# Switch1_copy.net
KiCad netlist of a schematic drawn in Altium Designer
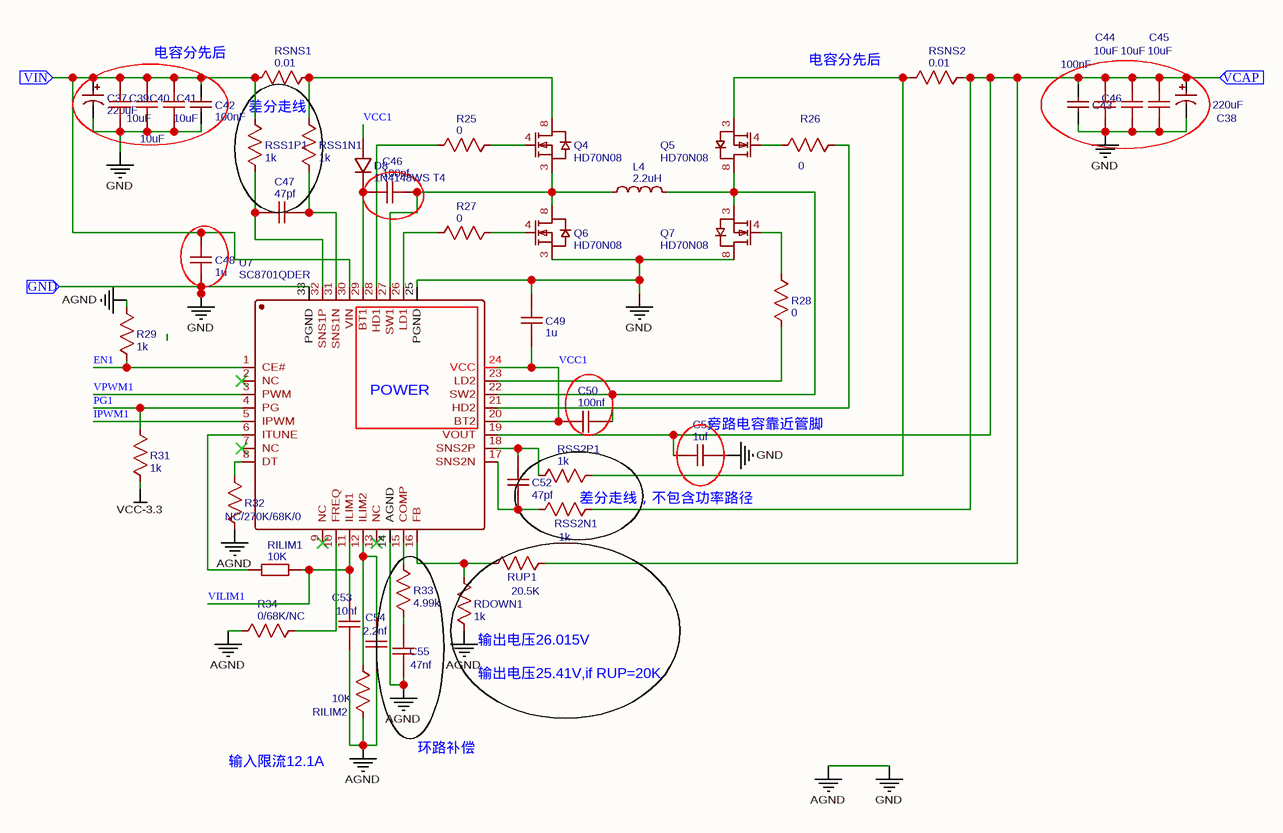
[diagram p0: Switch1 copy.SchDoc]

(export (version "E")
  (design (tool "Eeschema 10.0.6"))
  (components
    (comp (ref "C37")
      (value "220uF")
      (fields
        (field (name "BOM_MANUFACTURER PART") "DV221M050G105A")
        (field (name "BOM_SUPPLIER PART") "C65217")
      )
      (libsource (lib "") (part "root_3_220uF__1"))
    )
    (comp (ref "C38")
      (value "220uF")
      (fields
        (field (name "BOM_MANUFACTURER PART") "DV221M050G105A")
        (field (name "BOM_SUPPLIER PART") "C65217")
      )
      (libsource (lib "altium-import") (part "root_3_220uF_"))
    )
    (comp (ref "C39")
      (value "10uF")
      (fields
        (field (name "BOM_MANUFACTURER PART") "GRM31CR61H106KA12L")
        (field (name "BOM_SUPPLIER PART") "C77092")
      )
      (libsource (lib "altium-import") (part "root_1_10uF_"))
    )
    (comp (ref "C40")
      (value "10uF")
      (fields
        (field (name "BOM_MANUFACTURER PART") "GRM31CR61H106KA12L")
        (field (name "BOM_SUPPLIER PART") "C77092")
      )
      (libsource (lib "altium-import") (part "root_1_10uF_"))
    )
    (comp (ref "C41")
      (value "10uF")
      (fields
        (field (name "BOM_MANUFACTURER PART") "GRM31CR61H106KA12L")
        (field (name "BOM_SUPPLIER PART") "C77092")
      )
      (libsource (lib "altium-import") (part "root_1_10uF_"))
    )
    (comp (ref "C42")
      (value "100nF")
      (fields
        (field (name "BOM_MANUFACTURER PART") "CL10B104JB8NNNC")
        (field (name "BOM_SUPPLIER PART") "C1525")
      )
      (libsource (lib "altium-import") (part "root_1_100nF_"))
    )
    (comp (ref "C43")
      (value "100nF")
      (fields
        (field (name "BOM_MANUFACTURER PART") "CL10B104JB8NNNC")
        (field (name "BOM_SUPPLIER PART") "C1525")
      )
      (libsource (lib "altium-import") (part "root_1_100nF_"))
    )
    (comp (ref "C44")
      (value "10uF")
      (fields
        (field (name "BOM_MANUFACTURER PART") "GRM31CR61H106KA12L")
        (field (name "BOM_SUPPLIER PART") "C77092")
      )
      (libsource (lib "") (part "root_1_10uF__1"))
    )
    (comp (ref "C45")
      (value "10uF")
      (fields
        (field (name "BOM_MANUFACTURER PART") "GRM31CR61H106KA12L")
        (field (name "BOM_SUPPLIER PART") "C77092")
      )
      (libsource (lib "") (part "root_1_10uF__1"))
    )
    (comp (ref "C46") (value "100nf") (libsource (lib "altium-import") (part "root_3_100nf_")))
    (comp (ref "C47")
      (value "47pf")
      (fields (field (name "BOM_SUPPLIER PART") "C1567"))
      (libsource (lib "altium-import") (part "root_1_47pf_"))
    )
    (comp (ref "C48") (value "1u") (libsource (lib "altium-import") (part "root_0_1u_")))
    (comp (ref "C49") (value "1u") (libsource (lib "altium-import") (part "root_0_1u_")))
    (comp (ref "C50") (value "100nf") (libsource (lib "altium-import") (part "root_1_100nf_")))
    (comp (ref "C51") (value "1uf") (libsource (lib "altium-import") (part "root_1_1uf_")))
    (comp (ref "C52")
      (value "47pf")
      (fields (field (name "BOM_SUPPLIER PART") "C1567"))
      (libsource (lib "altium-import") (part "root_2_47pf_"))
    )
    (comp (ref "C53") (value "10nf") (libsource (lib "altium-import") (part "root_0_10nf_")))
    (comp (ref "C54") (value "2.2nf") (libsource (lib "altium-import") (part "root_0_2.2nf_")))
    (comp (ref "C55") (value "47nf") (libsource (lib "altium-import") (part "root_0_47nf_")))
    (comp (ref "D8")
      (value "1N4148WS T4")
      (fields (field (name "BOM_SUPPLIER PART") "C2128"))
      (libsource (lib "altium-import") (part "root_3_1N4148WS T4_"))
    )
    (comp (ref "L4")
      (value "2.2uH")
      (fields
        (field (name "BOM_SUPPLIER PART") "C241452")
        (field (name "BOM_MANUFACTURER PART") "YXMAC1770-2R2M-IGP")
        (field (name "CONTRIBUTOR") "LCSC")
      )
      (libsource (lib "altium-import") (part "root_0_2.2uH_"))
    )
    (comp (ref "NO1")
      (value "10uF")
      (fields
        (field (name "BOM_MANUFACTURER PART") "GRM31CR61H106KA12L")
        (field (name "BOM_SUPPLIER PART") "C77092")
      )
      (libsource (lib "") (part "root_1_10uF__1"))
    )
    (comp (ref "Q4")
      (value "HD70N08")
      (fields (field (name "BOM_SUPPLIER PART") "C190849") (field (name "CONTRIBUTOR") "LCSC"))
      (libsource (lib "altium-import") (part "root_0_HD70N08_"))
    )
    (comp (ref "Q5")
      (value "HD70N08")
      (fields (field (name "BOM_SUPPLIER PART") "C216254") (field (name "CONTRIBUTOR") "LCSC"))
      (libsource (lib "altium-import") (part "root_2_HD70N08_"))
    )
    (comp (ref "Q6")
      (value "HD70N08")
      (fields (field (name "BOM_SUPPLIER PART") "C216254") (field (name "CONTRIBUTOR") "LCSC"))
      (libsource (lib "altium-import") (part "root_0_HD70N08_"))
    )
    (comp (ref "Q7")
      (value "HD70N08")
      (fields (field (name "BOM_SUPPLIER PART") "C216254") (field (name "CONTRIBUTOR") "LCSC"))
      (libsource (lib "altium-import") (part "root_2_HD70N08_"))
    )
    (comp (ref "R25") (value "0") (libsource (lib "altium-import") (part "root_0_0_")))
    (comp (ref "R26") (value "0") (libsource (lib "altium-import") (part "root_0_0_")))
    (comp (ref "R27") (value "0") (libsource (lib "altium-import") (part "root_0_0_")))
    (comp (ref "R28") (value "0") (libsource (lib "altium-import") (part "root_1_0_")))
    (comp (ref "R29") (value "1k") (libsource (lib "altium-import") (part "root_1_1k_")))
    (comp (ref "R31") (value "1k") (libsource (lib "altium-import") (part "root_1_1k_")))
    (comp (ref "R32")
      (value "NC/270K/68K/0")
      (libsource (lib "altium-import") (part "root_1_NC/270K/68K/0_"))
    )
    (comp (ref "R33") (value "4.99k") (libsource (lib "altium-import") (part "root_1_4.99k_")))
    (comp (ref "R34") (value "0/68K/NC") (libsource (lib "altium-import") (part "root_0_0/68K/NC_")))
    (comp (ref "RDOWN1") (value "1k") (libsource (lib "altium-import") (part "root_1_1k_")))
    (comp (ref "RILIM1")
      (value "10K")
      (fields (field (name "BOM_SUPPLIER PART") "C25744") (field (name "CONTRIBUTOR") "LCSC"))
      (libsource (lib "altium-import") (part "root_0_10K_"))
    )
    (comp (ref "RILIM2") (value "10K") (libsource (lib "altium-import") (part "root_1_10K_")))
    (comp (ref "RSNS1")
      (value "0.01")
      (fields (field (name "BOM_SUPPLIER PART") "C236284"))
      (libsource (lib "altium-import") (part "root_0_0.01_"))
    )
    (comp (ref "RSNS2")
      (value "0.01")
      (fields (field (name "BOM_SUPPLIER PART") "C236284"))
      (libsource (lib "altium-import") (part "root_0_0.01_"))
    )
    (comp (ref "RSS1N1")
      (value "1k")
      (fields (field (name "BOM_SUPPLIER PART") "C319809"))
      (libsource (lib "altium-import") (part "root_1_1k_"))
    )
    (comp (ref "RSS1P1")
      (value "1k")
      (fields (field (name "BOM_SUPPLIER PART") "C319809"))
      (libsource (lib "altium-import") (part "root_1_1k_"))
    )
    (comp (ref "RSS2N1")
      (value "1k")
      (fields (field (name "BOM_SUPPLIER PART") "C319809"))
      (libsource (lib "altium-import") (part "root_0_1k_"))
    )
    (comp (ref "RSS2P1")
      (value "1k")
      (fields (field (name "BOM_SUPPLIER PART") "C319809"))
      (libsource (lib "altium-import") (part "root_0_1k_"))
    )
    (comp (ref "RUP1") (value "20.5K") (libsource (lib "altium-import") (part "root_0_20.5K_")))
    (comp (ref "U7")
      (value "SC8701QDER")
      (fields (field (name "BOM_SUPPLIER PART") "C252410") (field (name "CONTRIBUTOR") "LCSC"))
      (libsource (lib "altium-import") (part "root_0_SC8701QDER_"))
    )
  )
  (nets
    (net (code "1") (name "/EN1") (class "Default")
      (node (ref "R29") (pin "1") (pinfunction "1_1") (pintype "passive"))
      (node (ref "U7") (pin "1") (pinfunction "CE#_1") (pintype "passive"))
    )
    (net (code "2") (name "/IPWM1") (class "Default")
      (node (ref "U7") (pin "5") (pinfunction "IPWM_5") (pintype "passive"))
    )
    (net (code "3") (name "/PG1") (class "Default")
      (node (ref "R31") (pin "2") (pinfunction "2_2") (pintype "passive"))
      (node (ref "U7") (pin "4") (pinfunction "PG_4") (pintype "passive"))
    )
    (net (code "4") (name "/VCAP") (class "Default")
      (node (ref "C38") (pin "1") (pinfunction "1_1") (pintype "passive"))
      (node (ref "C43") (pin "2") (pinfunction "2_2") (pintype "passive"))
      (node (ref "C44") (pin "2") (pinfunction "2_2") (pintype "passive"))
      (node (ref "C45") (pin "2") (pinfunction "2_2") (pintype "passive"))
      (node (ref "C51") (pin "2") (pinfunction "2_2") (pintype "passive"))
      (node (ref "NO1") (pin "2") (pinfunction "2_2") (pintype "passive"))
      (node (ref "RSNS2") (pin "2") (pinfunction "2_2") (pintype "passive"))
      (node (ref "RSS2N1") (pin "2") (pinfunction "2_2") (pintype "passive"))
      (node (ref "RUP1") (pin "2") (pinfunction "2_2") (pintype "passive"))
      (node (ref "U7") (pin "19") (pinfunction "VOUT_19") (pintype "passive"))
    )
    (net (code "5") (name "/VCC1") (class "Default")
      (node (ref "C49") (pin "1") (pinfunction "1_1") (pintype "passive"))
      (node (ref "C50") (pin "2") (pinfunction "2_2") (pintype "passive"))
      (node (ref "D8") (pin "1") (pinfunction "A_1") (pintype "passive"))
      (node (ref "U7") (pin "20") (pinfunction "BT2_20") (pintype "passive"))
      (node (ref "U7") (pin "24") (pinfunction "VCC_24") (pintype "passive"))
    )
    (net (code "6") (name "/VILIM1") (class "Default")
      (node (ref "C53") (pin "2") (pinfunction "2_2") (pintype "passive"))
      (node (ref "RILIM1") (pin "2") (pinfunction "2_2") (pintype "passive"))
      (node (ref "U7") (pin "11") (pinfunction "ILIM1_11") (pintype "passive"))
    )
    (net (code "7") (name "/VIN") (class "Default")
      (node (ref "C37") (pin "1") (pinfunction "1_1") (pintype "passive"))
      (node (ref "C39") (pin "2") (pinfunction "2_2") (pintype "passive"))
      (node (ref "C40") (pin "2") (pinfunction "2_2") (pintype "passive"))
      (node (ref "C41") (pin "2") (pinfunction "2_2") (pintype "passive"))
      (node (ref "C42") (pin "2") (pinfunction "2_2") (pintype "passive"))
      (node (ref "C48") (pin "2") (pinfunction "2_2") (pintype "passive"))
      (node (ref "RSNS1") (pin "1") (pinfunction "1_1") (pintype "passive"))
      (node (ref "RSS1P1") (pin "2") (pinfunction "2_2") (pintype "passive"))
      (node (ref "U7") (pin "30") (pinfunction "VIN_30") (pintype "passive"))
    )
    (net (code "8") (name "/VPWM1") (class "Default")
      (node (ref "U7") (pin "3") (pinfunction "PWM_3") (pintype "passive"))
    )
    (net (code "9") (name "AGND") (class "Default")
      (node (ref "C37") (pin "2") (pinfunction "2_2") (pintype "passive"))
      (node (ref "C38") (pin "2") (pinfunction "2_2") (pintype "passive"))
      (node (ref "C39") (pin "1") (pinfunction "1_1") (pintype "passive"))
      (node (ref "C40") (pin "1") (pinfunction "1_1") (pintype "passive"))
      (node (ref "C41") (pin "1") (pinfunction "1_1") (pintype "passive"))
      (node (ref "C42") (pin "1") (pinfunction "1_1") (pintype "passive"))
      (node (ref "C43") (pin "1") (pinfunction "1_1") (pintype "passive"))
      (node (ref "C44") (pin "1") (pinfunction "1_1") (pintype "passive"))
      (node (ref "C45") (pin "1") (pinfunction "1_1") (pintype "passive"))
      (node (ref "C48") (pin "1") (pinfunction "1_1") (pintype "passive"))
      (node (ref "C49") (pin "2") (pinfunction "2_2") (pintype "passive"))
      (node (ref "C51") (pin "1") (pinfunction "1_1") (pintype "passive"))
      (node (ref "C53") (pin "1") (pinfunction "1_1") (pintype "passive"))
      (node (ref "C54") (pin "1") (pinfunction "1_1") (pintype "passive"))
      (node (ref "C55") (pin "1") (pinfunction "1_1") (pintype "passive"))
      (node (ref "NO1") (pin "1") (pinfunction "1_1") (pintype "passive"))
      (node (ref "Q6") (pin "3") (pinfunction "S_3") (pintype "passive"))
      (node (ref "Q7") (pin "8") (pinfunction "D_8") (pintype "passive"))
      (node (ref "R29") (pin "2") (pinfunction "2_2") (pintype "passive"))
      (node (ref "R32") (pin "1") (pinfunction "1_1") (pintype "passive"))
      (node (ref "R34") (pin "1") (pinfunction "1_1") (pintype "passive"))
      (node (ref "RDOWN1") (pin "1") (pinfunction "1_1") (pintype "passive"))
      (node (ref "RILIM2") (pin "1") (pinfunction "1_1") (pintype "passive"))
      (node (ref "U7") (pin "14") (pinfunction "AGND_14") (pintype "passive"))
      (node (ref "U7") (pin "25") (pinfunction "PGND_25") (pintype "passive"))
      (node (ref "U7") (pin "33") (pinfunction "PGND_33") (pintype "passive"))
    )
    (net (code "10") (name "Net-(C55-Pad2)") (class "Default")
      (node (ref "C55") (pin "2") (pinfunction "2_2") (pintype "passive"))
      (node (ref "R33") (pin "1") (pinfunction "1_1") (pintype "passive"))
    )
    (net (code "11") (name "Net-(D8-K)") (class "Default")
      (node (ref "C46") (pin "1") (pinfunction "1_1") (pintype "passive"))
      (node (ref "D8") (pin "2") (pinfunction "K_2") (pintype "passive"))
      (node (ref "U7") (pin "29") (pinfunction "BT1_29") (pintype "passive"))
    )
    (net (code "12") (name "Net-(Q4-D)") (class "Default")
      (node (ref "Q4") (pin "8") (pinfunction "D_8") (pintype "passive"))
      (node (ref "RSNS1") (pin "2") (pinfunction "2_2") (pintype "passive"))
      (node (ref "RSS1N1") (pin "2") (pinfunction "2_2") (pintype "passive"))
    )
    (net (code "13") (name "Net-(Q4-G)") (class "Default")
      (node (ref "Q4") (pin "4") (pinfunction "G_4") (pintype "passive"))
      (node (ref "R25") (pin "2") (pinfunction "2_2") (pintype "passive"))
    )
    (net (code "14") (name "Net-(Q4-S)") (class "Default")
      (node (ref "C46") (pin "2") (pinfunction "2_2") (pintype "passive"))
      (node (ref "L4") (pin "1") (pinfunction "1_1") (pintype "passive"))
      (node (ref "Q4") (pin "3") (pinfunction "S_3") (pintype "passive"))
      (node (ref "Q6") (pin "8") (pinfunction "D_8") (pintype "passive"))
      (node (ref "U7") (pin "27") (pinfunction "SW1_27") (pintype "passive"))
    )
    (net (code "15") (name "Net-(Q5-D)") (class "Default")
      (node (ref "C50") (pin "1") (pinfunction "1_1") (pintype "passive"))
      (node (ref "L4") (pin "2") (pinfunction "2_2") (pintype "passive"))
      (node (ref "Q5") (pin "8") (pinfunction "D_8") (pintype "passive"))
      (node (ref "Q7") (pin "3") (pinfunction "S_3") (pintype "passive"))
      (node (ref "U7") (pin "22") (pinfunction "SW2_22") (pintype "passive"))
    )
    (net (code "16") (name "Net-(Q5-G)") (class "Default")
      (node (ref "Q5") (pin "4") (pinfunction "G_4") (pintype "passive"))
      (node (ref "R26") (pin "1") (pinfunction "1_1") (pintype "passive"))
    )
    (net (code "17") (name "Net-(Q5-S)") (class "Default")
      (node (ref "Q5") (pin "3") (pinfunction "S_3") (pintype "passive"))
      (node (ref "RSNS2") (pin "1") (pinfunction "1_1") (pintype "passive"))
      (node (ref "RSS2P1") (pin "2") (pinfunction "2_2") (pintype "passive"))
    )
    (net (code "18") (name "Net-(Q6-G)") (class "Default")
      (node (ref "Q6") (pin "4") (pinfunction "G_4") (pintype "passive"))
      (node (ref "R27") (pin "2") (pinfunction "2_2") (pintype "passive"))
    )
    (net (code "19") (name "Net-(Q7-G)") (class "Default")
      (node (ref "Q7") (pin "4") (pinfunction "G_4") (pintype "passive"))
      (node (ref "R28") (pin "2") (pinfunction "2_2") (pintype "passive"))
    )
    (net (code "20") (name "Net-(U7-COMP)") (class "Default")
      (node (ref "R33") (pin "2") (pinfunction "2_2") (pintype "passive"))
      (node (ref "U7") (pin "15") (pinfunction "COMP_15") (pintype "passive"))
    )
    (net (code "21") (name "Net-(U7-DT)") (class "Default")
      (node (ref "R32") (pin "2") (pinfunction "2_2") (pintype "passive"))
      (node (ref "U7") (pin "8") (pinfunction "DT_8") (pintype "passive"))
    )
    (net (code "22") (name "Net-(U7-FB)") (class "Default")
      (node (ref "RDOWN1") (pin "2") (pinfunction "2_2") (pintype "passive"))
      (node (ref "RUP1") (pin "1") (pinfunction "1_1") (pintype "passive"))
      (node (ref "U7") (pin "16") (pinfunction "FB_16") (pintype "passive"))
    )
    (net (code "23") (name "Net-(U7-FREQ)") (class "Default")
      (node (ref "R34") (pin "2") (pinfunction "2_2") (pintype "passive"))
      (node (ref "U7") (pin "10") (pinfunction "FREQ_10") (pintype "passive"))
    )
    (net (code "24") (name "Net-(U7-HD1)") (class "Default")
      (node (ref "R25") (pin "1") (pinfunction "1_1") (pintype "passive"))
      (node (ref "U7") (pin "28") (pinfunction "HD1_28") (pintype "passive"))
    )
    (net (code "25") (name "Net-(U7-HD2)") (class "Default")
      (node (ref "R26") (pin "2") (pinfunction "2_2") (pintype "passive"))
      (node (ref "U7") (pin "21") (pinfunction "HD2_21") (pintype "passive"))
    )
    (net (code "26") (name "Net-(U7-ILIM2)") (class "Default")
      (node (ref "C54") (pin "2") (pinfunction "2_2") (pintype "passive"))
      (node (ref "RILIM2") (pin "2") (pinfunction "2_2") (pintype "passive"))
      (node (ref "U7") (pin "12") (pinfunction "ILIM2_12") (pintype "passive"))
    )
    (net (code "27") (name "Net-(U7-ITUNE)") (class "Default")
      (node (ref "RILIM1") (pin "1") (pinfunction "1_1") (pintype "passive"))
      (node (ref "U7") (pin "6") (pinfunction "ITUNE_6") (pintype "passive"))
    )
    (net (code "28") (name "Net-(U7-LD1)") (class "Default")
      (node (ref "R27") (pin "1") (pinfunction "1_1") (pintype "passive"))
      (node (ref "U7") (pin "26") (pinfunction "LD1_26") (pintype "passive"))
    )
    (net (code "29") (name "Net-(U7-LD2)") (class "Default")
      (node (ref "R28") (pin "1") (pinfunction "1_1") (pintype "passive"))
      (node (ref "U7") (pin "23") (pinfunction "LD2_23") (pintype "passive"))
    )
    (net (code "30") (name "Net-(U7-SNS1N)") (class "Default")
      (node (ref "C47") (pin "1") (pinfunction "1_1") (pintype "passive"))
      (node (ref "RSS1N1") (pin "1") (pinfunction "1_1") (pintype "passive"))
      (node (ref "U7") (pin "31") (pinfunction "SNS1N_31") (pintype "passive"))
    )
    (net (code "31") (name "Net-(U7-SNS1P)") (class "Default")
      (node (ref "C47") (pin "2") (pinfunction "2_2") (pintype "passive"))
      (node (ref "RSS1P1") (pin "1") (pinfunction "1_1") (pintype "passive"))
      (node (ref "U7") (pin "32") (pinfunction "SNS1P_32") (pintype "passive"))
    )
    (net (code "32") (name "Net-(U7-SNS2N)") (class "Default")
      (node (ref "C52") (pin "2") (pinfunction "2_2") (pintype "passive"))
      (node (ref "RSS2N1") (pin "1") (pinfunction "1_1") (pintype "passive"))
      (node (ref "U7") (pin "17") (pinfunction "SNS2N_17") (pintype "passive"))
    )
    (net (code "33") (name "Net-(U7-SNS2P)") (class "Default")
      (node (ref "C52") (pin "1") (pinfunction "1_1") (pintype "passive"))
      (node (ref "RSS2P1") (pin "1") (pinfunction "1_1") (pintype "passive"))
      (node (ref "U7") (pin "18") (pinfunction "SNS2P_18") (pintype "passive"))
    )
    (net (code "34") (name "VCC-3.3") (class "Default")
      (node (ref "R31") (pin "1") (pinfunction "1_1") (pintype "passive"))
    )
    (net (code "35") (name "unconnected-(U7-NC-Pad2)") (class "Default")
      (node (ref "U7") (pin "2") (pinfunction "NC_2") (pintype "passive+no_connect"))
    )
    (net (code "36") (name "unconnected-(U7-NC-Pad7)") (class "Default")
      (node (ref "U7") (pin "7") (pinfunction "NC_7") (pintype "passive+no_connect"))
    )
    (net (code "37") (name "unconnected-(U7-NC-Pad9)") (class "Default")
      (node (ref "U7") (pin "9") (pinfunction "NC_9") (pintype "passive+no_connect"))
    )
    (net (code "38") (name "unconnected-(U7-NC-Pad13)") (class "Default")
      (node (ref "U7") (pin "13") (pinfunction "NC_13") (pintype "passive+no_connect"))
    )
  )
)
